# Keyboard.net
KiCad netlist of a schematic drawn in Altium Designer
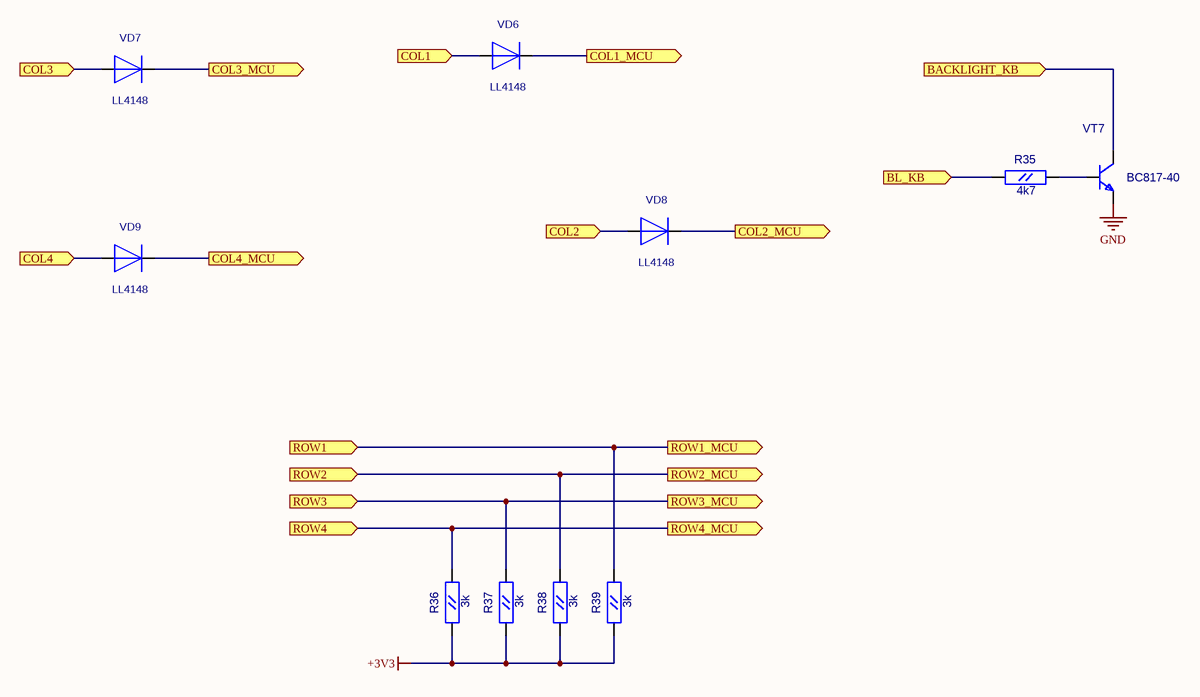
[diagram p0: Keyboard.SchDoc]

(export (version "E")
  (design (tool "Eeschema 10.0.6"))
  (components
    (comp (ref "R35")
      (value "4k7")
      (footprint "RC0603")
      (description "RC0603")
      (libsource (lib "gprs_modem_2") (part "RC0603"))
    )
    (comp (ref "R36")
      (value "3k")
      (footprint "RC0603")
      (description "RC0603")
      (libsource (lib "gprs_modem_2") (part "RC0603"))
    )
    (comp (ref "R37")
      (value "3k")
      (footprint "RC0603")
      (description "RC0603")
      (libsource (lib "gprs_modem_2") (part "RC0603"))
    )
    (comp (ref "R38")
      (value "3k")
      (footprint "RC0603")
      (description "RC0603")
      (libsource (lib "gprs_modem_2") (part "RC0603"))
    )
    (comp (ref "R39")
      (value "3k")
      (footprint "RC0603")
      (description "RC0603")
      (libsource (lib "gprs_modem_2") (part "RC0603"))
    )
    (comp (ref "VD6") (value "LL4148") (footprint "SOD-80") (libsource (lib "gprs_modem_2") (part "LL4148")))
    (comp (ref "VD7") (value "LL4148") (footprint "SOD-80") (libsource (lib "gprs_modem_2") (part "LL4148")))
    (comp (ref "VD8") (value "LL4148") (footprint "SOD-80") (libsource (lib "gprs_modem_2") (part "LL4148")))
    (comp (ref "VD9") (value "LL4148") (footprint "SOD-80") (libsource (lib "gprs_modem_2") (part "LL4148")))
    (comp (ref "VT7")
      (value "BC817-40")
      (footprint "SOT-23(123)")
      (description "NPN 500ma transistor")
      (libsource (lib "gprs_modem_2") (part "BC846BLT1"))
    )
  )
  (nets
    (net (code "1") (name "+3V3") (class "Default")
      (node (ref "R36") (pin "1") (pinfunction "A_1") (pintype "passive"))
      (node (ref "R37") (pin "1") (pinfunction "A_1") (pintype "passive"))
      (node (ref "R38") (pin "1") (pinfunction "A_1") (pintype "passive"))
      (node (ref "R39") (pin "1") (pinfunction "A_1") (pintype "passive"))
    )
    (net (code "2") (name "/BACKLIGHT_KB") (class "Default")
      (node (ref "VT7") (pin "3") (pinfunction "C_3") (pintype "passive"))
    )
    (net (code "3") (name "/BL_KB") (class "Default")
      (node (ref "R35") (pin "1") (pinfunction "A_1") (pintype "passive"))
    )
    (net (code "4") (name "/COL1") (class "Default")
      (node (ref "VD6") (pin "1") (pinfunction "-_1") (pintype "passive"))
    )
    (net (code "5") (name "/COL1_MCU") (class "Default")
      (node (ref "VD6") (pin "2") (pinfunction "+_2") (pintype "passive"))
    )
    (net (code "6") (name "/COL2") (class "Default")
      (node (ref "VD8") (pin "1") (pinfunction "-_1") (pintype "passive"))
    )
    (net (code "7") (name "/COL2_MCU") (class "Default")
      (node (ref "VD8") (pin "2") (pinfunction "+_2") (pintype "passive"))
    )
    (net (code "8") (name "/COL3") (class "Default")
      (node (ref "VD7") (pin "1") (pinfunction "-_1") (pintype "passive"))
    )
    (net (code "9") (name "/COL3_MCU") (class "Default")
      (node (ref "VD7") (pin "2") (pinfunction "+_2") (pintype "passive"))
    )
    (net (code "10") (name "/COL4") (class "Default")
      (node (ref "VD9") (pin "1") (pinfunction "-_1") (pintype "passive"))
    )
    (net (code "11") (name "/COL4_MCU") (class "Default")
      (node (ref "VD9") (pin "2") (pinfunction "+_2") (pintype "passive"))
    )
    (net (code "12") (name "/ROW1") (class "Default")
      (node (ref "R39") (pin "2") (pinfunction "B_2") (pintype "passive"))
    )
    (net (code "13") (name "/ROW2") (class "Default")
      (node (ref "R38") (pin "2") (pinfunction "B_2") (pintype "passive"))
    )
    (net (code "14") (name "/ROW3") (class "Default")
      (node (ref "R37") (pin "2") (pinfunction "B_2") (pintype "passive"))
    )
    (net (code "15") (name "/ROW4") (class "Default")
      (node (ref "R36") (pin "2") (pinfunction "B_2") (pintype "passive"))
    )
    (net (code "16") (name "GND") (class "Default")
      (node (ref "VT7") (pin "2") (pinfunction "E_2") (pintype "passive"))
    )
    (net (code "17") (name "Net-(R35-B)") (class "Default")
      (node (ref "R35") (pin "2") (pinfunction "B_2") (pintype "passive"))
      (node (ref "VT7") (pin "1") (pinfunction "B_1") (pintype "passive"))
    )
  )
)
